# Schematic.net
KiCad netlist of a schematic drawn in Altium Designer
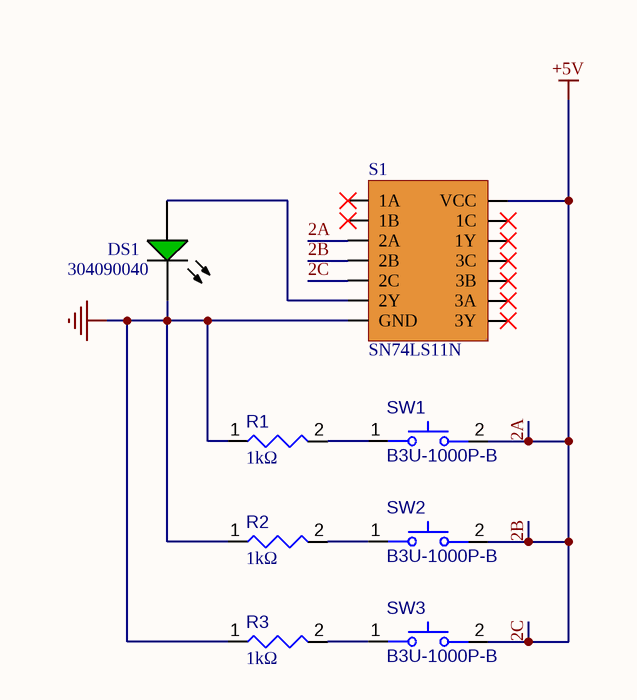
[diagram p0: Schematic.SchDoc]

(export (version "E")
  (design (tool "Eeschema 10.0.6"))
  (components
    (comp (ref "DS1")
      (value "304090040")
      (footprint "LED-2P-2.28-3MM")
      (description "Green LED, 80 mW, 20 mA, -25 to 85 degC, 2-Pin THD")
      (fields (field (name "MANUFACTURER") "Shenzhen CGX"))
      (libsource (lib "Middlesex University") (part "LED-GREEN-AK-2"))
    )
    (comp (ref "R1")
      (value "1kΩ")
      (footprint "RESC0402(1005)_L")
      (description "1K 0.063W 5% 0402 (1005 Metric)  SMD")
      (fields (field (name "POWER") "63mW") (field (name "TOLERANCE") "5%"))
      (libsource (lib "Middlesex University") (part "1KR2J"))
    )
    (comp (ref "R2")
      (value "1kΩ")
      (footprint "RESC0402(1005)_L")
      (description "1K 0.063W 5% 0402 (1005 Metric)  SMD")
      (fields (field (name "POWER") "63mW") (field (name "TOLERANCE") "5%"))
      (libsource (lib "Middlesex University") (part "1KR2J"))
    )
    (comp (ref "R3")
      (value "1kΩ")
      (footprint "RESC0402(1005)_L")
      (description "1K 0.063W 5% 0402 (1005 Metric)  SMD")
      (fields (field (name "POWER") "63mW") (field (name "TOLERANCE") "5%"))
      (libsource (lib "Middlesex University") (part "1KR2J"))
    )
    (comp (ref "S1")
      (value "SN74LS11N")
      (description "AND Gate 3-Element 3-IN Bipolar 14-Pin PDIP Tube")
      (fields (field (name "MANUFACTURER") "Texas Instruments"))
      (libsource (lib "Schematic Library") (part "SN74LS11N"))
    )
    (comp (ref "SW1")
      (value "B3U-1000P-B")
      (footprint "OMRON-B3U-1000P-2-B_V")
      (libsource (lib "Middlesex University") (part "CMP-00164-6"))
    )
    (comp (ref "SW2")
      (value "B3U-1000P-B")
      (footprint "OMRON-B3U-1000P-2-B_V")
      (libsource (lib "Middlesex University") (part "CMP-00164-6"))
    )
    (comp (ref "SW3")
      (value "B3U-1000P-B")
      (footprint "OMRON-B3U-1000P-2-B_V")
      (libsource (lib "Middlesex University") (part "CMP-00164-6"))
    )
  )
  (nets
    (net (code "1") (name "+5V") (class "Default")
      (node (ref "S1") (pin "14") (pinfunction "VCC_14") (pintype "passive"))
      (node (ref "S1") (pin "3") (pinfunction "2A_3") (pintype "passive"))
      (node (ref "S1") (pin "4") (pinfunction "2B_4") (pintype "passive"))
      (node (ref "S1") (pin "5") (pinfunction "2C_5") (pintype "passive"))
      (node (ref "SW1") (pin "2") (pinfunction "2_2") (pintype "passive"))
      (node (ref "SW2") (pin "2") (pinfunction "2_2") (pintype "passive"))
      (node (ref "SW3") (pin "2") (pinfunction "2_2") (pintype "passive"))
    )
    (net (code "2") (name "GND") (class "Default")
      (node (ref "DS1") (pin "2") (pinfunction "K_2") (pintype "passive"))
      (node (ref "R1") (pin "1") (pinfunction "1_1") (pintype "passive"))
      (node (ref "R2") (pin "1") (pinfunction "1_1") (pintype "passive"))
      (node (ref "R3") (pin "1") (pinfunction "1_1") (pintype "passive"))
      (node (ref "S1") (pin "7") (pinfunction "GND_7") (pintype "passive"))
    )
    (net (code "3") (name "Net-(DS1-A)") (class "Default")
      (node (ref "DS1") (pin "1") (pinfunction "A_1") (pintype "passive"))
      (node (ref "S1") (pin "6") (pinfunction "2Y_6") (pintype "passive"))
    )
    (net (code "4") (name "Net-(R1-Pad2)") (class "Default")
      (node (ref "R1") (pin "2") (pinfunction "2_2") (pintype "passive"))
      (node (ref "SW1") (pin "1") (pinfunction "1_1") (pintype "passive"))
    )
    (net (code "5") (name "Net-(R2-Pad2)") (class "Default")
      (node (ref "R2") (pin "2") (pinfunction "2_2") (pintype "passive"))
      (node (ref "SW2") (pin "1") (pinfunction "1_1") (pintype "passive"))
    )
    (net (code "6") (name "Net-(R3-Pad2)") (class "Default")
      (node (ref "R3") (pin "2") (pinfunction "2_2") (pintype "passive"))
      (node (ref "SW3") (pin "1") (pinfunction "1_1") (pintype "passive"))
    )
    (net (code "7") (name "unconnected-(S1-1A-Pad1)") (class "Default")
      (node (ref "S1") (pin "1") (pinfunction "1A_1") (pintype "passive+no_connect"))
    )
    (net (code "8") (name "unconnected-(S1-1B-Pad2)") (class "Default")
      (node (ref "S1") (pin "2") (pinfunction "1B_2") (pintype "passive+no_connect"))
    )
    (net (code "9") (name "unconnected-(S1-1C-Pad13)") (class "Default")
      (node (ref "S1") (pin "13") (pinfunction "1C_13") (pintype "passive+no_connect"))
    )
    (net (code "10") (name "unconnected-(S1-1Y-Pad12)") (class "Default")
      (node (ref "S1") (pin "12") (pinfunction "1Y_12") (pintype "passive+no_connect"))
    )
    (net (code "11") (name "unconnected-(S1-3A-Pad9)") (class "Default")
      (node (ref "S1") (pin "9") (pinfunction "3A_9") (pintype "passive+no_connect"))
    )
    (net (code "12") (name "unconnected-(S1-3B-Pad10)") (class "Default")
      (node (ref "S1") (pin "10") (pinfunction "3B_10") (pintype "passive+no_connect"))
    )
    (net (code "13") (name "unconnected-(S1-3C-Pad11)") (class "Default")
      (node (ref "S1") (pin "11") (pinfunction "3C_11") (pintype "passive+no_connect"))
    )
    (net (code "14") (name "unconnected-(S1-3Y-Pad8)") (class "Default")
      (node (ref "S1") (pin "8") (pinfunction "3Y_8") (pintype "passive+no_connect"))
    )
  )
)
